# HB-UNI-SenAct-4-4-RC_V2_0.net
KiCad netlist of a schematic drawn in EAGLE
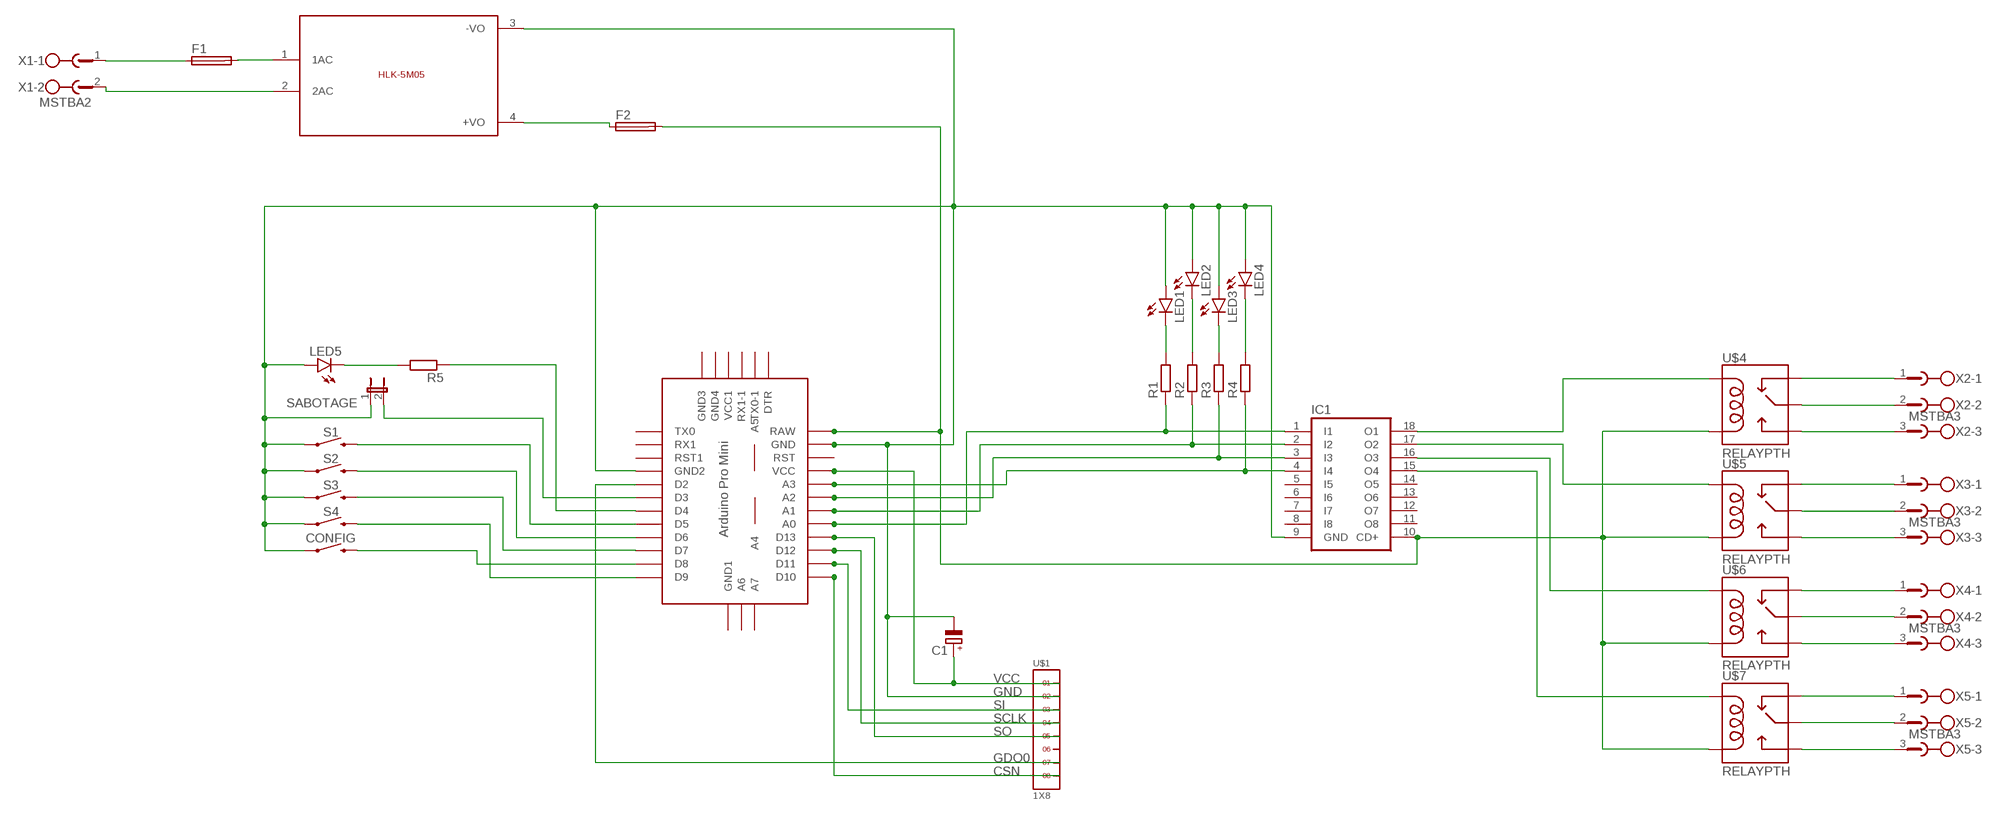
[diagram p0: schematic, sheet 1]

(export (version "E")
  (design (tool "Eeschema 10.0.6"))
  (components
    (comp (ref "C1")
      (value "CPOL-EUE2.5-5")
      (footprint "eagle-import:E2,5-5")
      (libsource (lib "eagle-import") (part "CPOL-EUE2.5-5"))
    )
    (comp (ref "CONFIG")
      (value "MOMENTARY-SWITCH-SPST-PTH-6.0MM-KIT")
      (footprint "eagle-import:TACTILE_SWITCH_PTH_6.0MM_KIT")
      (libsource (lib "eagle-import") (part "MOMENTARY-SWITCH-SPST-PTH-6.0MM-KIT"))
    )
    (comp (ref "F1")
      (value "SH22,5A")
      (footprint "eagle-import:SH22,5A")
      (fields (field (name "MPN") "0031.7701.11"))
      (libsource (lib "eagle-import") (part "SH22,5A"))
    )
    (comp (ref "F2")
      (value "SH22,5A")
      (footprint "eagle-import:SH22,5A")
      (fields (field (name "MPN") "0031.7701.11"))
      (libsource (lib "eagle-import") (part "SH22,5A"))
    )
    (comp (ref "IC1")
      (value "ULN2803A")
      (footprint "eagle-import:DIL18")
      (libsource (lib "eagle-import") (part "ULN2803A"))
    )
    (comp (ref "LED1")
      (value "LED3MM")
      (footprint "eagle-import:LED3MM")
      (libsource (lib "eagle-import") (part "LED3MM"))
    )
    (comp (ref "LED2")
      (value "LED3MM")
      (footprint "eagle-import:LED3MM")
      (libsource (lib "eagle-import") (part "LED3MM"))
    )
    (comp (ref "LED3")
      (value "LED3MM")
      (footprint "eagle-import:LED3MM")
      (libsource (lib "eagle-import") (part "LED3MM"))
    )
    (comp (ref "LED4")
      (value "LED3MM")
      (footprint "eagle-import:LED3MM")
      (libsource (lib "eagle-import") (part "LED3MM"))
    )
    (comp (ref "LED5")
      (value "LED3MM")
      (footprint "eagle-import:LED3MM")
      (libsource (lib "eagle-import") (part "LED3MM"))
    )
    (comp (ref "R1")
      (value "R-EU_0309/10")
      (footprint "eagle-import:0309_10")
      (libsource (lib "eagle-import") (part "R-EU_0309/10"))
    )
    (comp (ref "R2")
      (value "R-EU_0309/10")
      (footprint "eagle-import:0309_10")
      (libsource (lib "eagle-import") (part "R-EU_0309/10"))
    )
    (comp (ref "R3")
      (value "R-EU_0309/10")
      (footprint "eagle-import:0309_10")
      (libsource (lib "eagle-import") (part "R-EU_0309/10"))
    )
    (comp (ref "R4")
      (value "R-EU_0309/10")
      (footprint "eagle-import:0309_10")
      (libsource (lib "eagle-import") (part "R-EU_0309/10"))
    )
    (comp (ref "R5")
      (value "R-EU_0309/10")
      (footprint "eagle-import:0309_10")
      (libsource (lib "eagle-import") (part "R-EU_0309/10"))
    )
    (comp (ref "S1")
      (value "MOMENTARY-SWITCH-SPST-PTH-6.0MM-KIT")
      (footprint "eagle-import:TACTILE_SWITCH_PTH_6.0MM_KIT")
      (libsource (lib "eagle-import") (part "MOMENTARY-SWITCH-SPST-PTH-6.0MM-KIT"))
    )
    (comp (ref "S2")
      (value "MOMENTARY-SWITCH-SPST-PTH-6.0MM-KIT")
      (footprint "eagle-import:TACTILE_SWITCH_PTH_6.0MM_KIT")
      (libsource (lib "eagle-import") (part "MOMENTARY-SWITCH-SPST-PTH-6.0MM-KIT"))
    )
    (comp (ref "S3")
      (value "MOMENTARY-SWITCH-SPST-PTH-6.0MM-KIT")
      (footprint "eagle-import:TACTILE_SWITCH_PTH_6.0MM_KIT")
      (libsource (lib "eagle-import") (part "MOMENTARY-SWITCH-SPST-PTH-6.0MM-KIT"))
    )
    (comp (ref "S4")
      (value "MOMENTARY-SWITCH-SPST-PTH-6.0MM-KIT")
      (footprint "eagle-import:TACTILE_SWITCH_PTH_6.0MM_KIT")
      (libsource (lib "eagle-import") (part "MOMENTARY-SWITCH-SPST-PTH-6.0MM-KIT"))
    )
    (comp (ref "SABOTAGE")
      (value "JP1E")
      (footprint "eagle-import:JP1")
      (libsource (lib "eagle-import") (part "JP1E"))
    )
    (comp (ref "U$1")
      (value "1X8")
      (footprint "eagle-import:1X8")
      (libsource (lib "eagle-import") (part "1X8"))
    )
    (comp (ref "U$2")
      (value "ABK-PRO-MINI")
      (footprint "eagle-import:ABK-PRO-MINI")
      (libsource (lib "eagle-import") (part "ABK-PRO-MINI"))
    )
    (comp (ref "U$3")
      (value "5VDC/5W")
      (footprint "eagle-import:HLK-5M05")
      (libsource (lib "eagle-import") (part "HLK-5M05"))
    )
    (comp (ref "U$4")
      (value "RELAYPTH")
      (footprint "eagle-import:SRD-05VDC-SL-C")
      (libsource (lib "eagle-import") (part "RELAYPTH"))
    )
    (comp (ref "U$5")
      (value "RELAYPTH")
      (footprint "eagle-import:SRD-05VDC-SL-C")
      (libsource (lib "eagle-import") (part "RELAYPTH"))
    )
    (comp (ref "U$6")
      (value "RELAYPTH")
      (footprint "eagle-import:SRD-05VDC-SL-C")
      (libsource (lib "eagle-import") (part "RELAYPTH"))
    )
    (comp (ref "U$7")
      (value "RELAYPTH")
      (footprint "eagle-import:SRD-05VDC-SL-C")
      (libsource (lib "eagle-import") (part "RELAYPTH"))
    )
    (comp (ref "X1")
      (value "MSTBA2")
      (footprint "eagle-import:MSTBA2")
      (fields (field (name "MF") "FARNELL") (field (name "MPN") "1757242"))
      (libsource (lib "eagle-import") (part "MSTBA2"))
    )
    (comp (ref "X2")
      (value "MSTBA3")
      (footprint "eagle-import:MSTBA3")
      (fields (field (name "MF") "FARNELL") (field (name "MPN") "1757255"))
      (libsource (lib "eagle-import") (part "MSTBA3"))
    )
    (comp (ref "X3")
      (value "MSTBA3")
      (footprint "eagle-import:MSTBA3")
      (fields (field (name "MF") "FARNELL") (field (name "MPN") "1757255"))
      (libsource (lib "eagle-import") (part "MSTBA3"))
    )
    (comp (ref "X4")
      (value "MSTBA3")
      (footprint "eagle-import:MSTBA3")
      (fields (field (name "MF") "FARNELL") (field (name "MPN") "1757255"))
      (libsource (lib "eagle-import") (part "MSTBA3"))
    )
    (comp (ref "X5")
      (value "MSTBA3")
      (footprint "eagle-import:MSTBA3")
      (fields (field (name "MF") "FARNELL") (field (name "MPN") "1757255"))
      (libsource (lib "eagle-import") (part "MSTBA3"))
    )
  )
  (nets
    (net (code "1") (name "/CSN") (class "Default")
      (node (ref "U$1") (pin "8") (pinfunction "8_8") (pintype "bidirectional"))
      (node (ref "U$2") (pin "D10") (pinfunction "D10_D10") (pintype "bidirectional"))
    )
    (net (code "2") (name "/GDO0") (class "Default")
      (node (ref "U$1") (pin "7") (pinfunction "7_7") (pintype "bidirectional"))
      (node (ref "U$2") (pin "D2") (pinfunction "D2_D2") (pintype "bidirectional"))
    )
    (net (code "3") (name "/GND") (class "Default")
      (node (ref "C1") (pin "-") (pinfunction "-_-") (pintype "passive"))
      (node (ref "CONFIG") (pin "1") (pinfunction "1_1") (pintype "passive"))
      (node (ref "IC1") (pin "9") (pinfunction "GND_9") (pintype "power_in"))
      (node (ref "LED1") (pin "A") (pinfunction "A_A") (pintype "passive"))
      (node (ref "LED2") (pin "A") (pinfunction "A_A") (pintype "passive"))
      (node (ref "LED3") (pin "A") (pinfunction "A_A") (pintype "passive"))
      (node (ref "LED4") (pin "A") (pinfunction "A_A") (pintype "passive"))
      (node (ref "LED5") (pin "A") (pinfunction "A_A") (pintype "passive"))
      (node (ref "S1") (pin "1") (pinfunction "1_1") (pintype "passive"))
      (node (ref "S2") (pin "1") (pinfunction "1_1") (pintype "passive"))
      (node (ref "S3") (pin "1") (pinfunction "1_1") (pintype "passive"))
      (node (ref "S4") (pin "1") (pinfunction "1_1") (pintype "passive"))
      (node (ref "SABOTAGE") (pin "1") (pinfunction "1_1") (pintype "passive"))
      (node (ref "U$1") (pin "2") (pinfunction "2_2") (pintype "bidirectional"))
      (node (ref "U$2") (pin "GND") (pinfunction "GND_GND") (pintype "bidirectional"))
      (node (ref "U$2") (pin "GND1") (pinfunction "GND2_GND1") (pintype "bidirectional"))
      (node (ref "U$3") (pin "3") (pinfunction "-VO_3") (pintype "bidirectional"))
    )
    (net (code "4") (name "/SCLK") (class "Default")
      (node (ref "U$1") (pin "4") (pinfunction "4_4") (pintype "bidirectional"))
      (node (ref "U$2") (pin "D12") (pinfunction "D12_D12") (pintype "bidirectional"))
    )
    (net (code "5") (name "/SI") (class "Default")
      (node (ref "U$1") (pin "3") (pinfunction "3_3") (pintype "bidirectional"))
      (node (ref "U$2") (pin "D11") (pinfunction "D11_D11") (pintype "bidirectional"))
    )
    (net (code "6") (name "/SO") (class "Default")
      (node (ref "U$1") (pin "5") (pinfunction "5_5") (pintype "bidirectional"))
      (node (ref "U$2") (pin "D13") (pinfunction "D13_D13") (pintype "bidirectional"))
    )
    (net (code "7") (name "/VCC") (class "Default")
      (node (ref "C1") (pin "+") (pinfunction "+_+") (pintype "passive"))
      (node (ref "U$1") (pin "1") (pinfunction "1_1") (pintype "bidirectional"))
      (node (ref "U$2") (pin "VCC") (pinfunction "VCC_VCC") (pintype "bidirectional"))
    )
    (net (code "8") (name "Net-(CONFIG-2)") (class "Default")
      (node (ref "CONFIG") (pin "3") (pinfunction "2_3") (pintype "passive"))
      (node (ref "U$2") (pin "D8") (pinfunction "D8_D8") (pintype "bidirectional"))
    )
    (net (code "9") (name "Net-(F1-Pad1)") (class "Default")
      (node (ref "F1") (pin "1") (pinfunction "1_1") (pintype "passive"))
      (node (ref "X1") (pin "1") (pinfunction "1_1") (pintype "passive"))
    )
    (net (code "10") (name "Net-(IC1-CD+)") (class "Default")
      (node (ref "F2") (pin "2") (pinfunction "2_2") (pintype "passive"))
      (node (ref "IC1") (pin "10") (pinfunction "CD+_10") (pintype "passive"))
      (node (ref "U$2") (pin "RAW") (pinfunction "RAW_RAW") (pintype "bidirectional"))
      (node (ref "U$4") (pin "COIL0") (pinfunction "COIL0_COIL0") (pintype "bidirectional"))
      (node (ref "U$5") (pin "COIL0") (pinfunction "COIL0_COIL0") (pintype "bidirectional"))
      (node (ref "U$6") (pin "COIL0") (pinfunction "COIL0_COIL0") (pintype "bidirectional"))
      (node (ref "U$7") (pin "COIL0") (pinfunction "COIL0_COIL0") (pintype "bidirectional"))
    )
    (net (code "11") (name "Net-(IC1-I1)") (class "Default")
      (node (ref "IC1") (pin "1") (pinfunction "I1_1") (pintype "input"))
      (node (ref "R1") (pin "1") (pinfunction "1_1") (pintype "passive"))
      (node (ref "U$2") (pin "A0") (pinfunction "A0_A0") (pintype "bidirectional"))
    )
    (net (code "12") (name "Net-(IC1-I2)") (class "Default")
      (node (ref "IC1") (pin "2") (pinfunction "I2_2") (pintype "input"))
      (node (ref "R2") (pin "1") (pinfunction "1_1") (pintype "passive"))
      (node (ref "U$2") (pin "A1") (pinfunction "A1_A1") (pintype "bidirectional"))
    )
    (net (code "13") (name "Net-(IC1-I3)") (class "Default")
      (node (ref "IC1") (pin "3") (pinfunction "I3_3") (pintype "input"))
      (node (ref "R3") (pin "1") (pinfunction "1_1") (pintype "passive"))
      (node (ref "U$2") (pin "A2") (pinfunction "A2_A2") (pintype "bidirectional"))
    )
    (net (code "14") (name "Net-(IC1-I4)") (class "Default")
      (node (ref "IC1") (pin "4") (pinfunction "I4_4") (pintype "input"))
      (node (ref "R4") (pin "1") (pinfunction "1_1") (pintype "passive"))
      (node (ref "U$2") (pin "A3") (pinfunction "A3_A3") (pintype "bidirectional"))
    )
    (net (code "15") (name "Net-(IC1-O1)") (class "Default")
      (node (ref "IC1") (pin "18") (pinfunction "O1_18") (pintype "open_collector"))
      (node (ref "U$4") (pin "COIL1") (pinfunction "COIL1_COIL1") (pintype "bidirectional"))
    )
    (net (code "16") (name "Net-(IC1-O2)") (class "Default")
      (node (ref "IC1") (pin "17") (pinfunction "O2_17") (pintype "open_collector"))
      (node (ref "U$5") (pin "COIL1") (pinfunction "COIL1_COIL1") (pintype "bidirectional"))
    )
    (net (code "17") (name "Net-(IC1-O3)") (class "Default")
      (node (ref "IC1") (pin "16") (pinfunction "O3_16") (pintype "open_collector"))
      (node (ref "U$6") (pin "COIL1") (pinfunction "COIL1_COIL1") (pintype "bidirectional"))
    )
    (net (code "18") (name "Net-(IC1-O4)") (class "Default")
      (node (ref "IC1") (pin "15") (pinfunction "O4_15") (pintype "open_collector"))
      (node (ref "U$7") (pin "COIL1") (pinfunction "COIL1_COIL1") (pintype "bidirectional"))
    )
    (net (code "19") (name "Net-(LED1-C)") (class "Default")
      (node (ref "LED1") (pin "K") (pinfunction "C_K") (pintype "passive"))
      (node (ref "R1") (pin "2") (pinfunction "2_2") (pintype "passive"))
    )
    (net (code "20") (name "Net-(LED2-C)") (class "Default")
      (node (ref "LED2") (pin "K") (pinfunction "C_K") (pintype "passive"))
      (node (ref "R2") (pin "2") (pinfunction "2_2") (pintype "passive"))
    )
    (net (code "21") (name "Net-(LED3-C)") (class "Default")
      (node (ref "LED3") (pin "K") (pinfunction "C_K") (pintype "passive"))
      (node (ref "R3") (pin "2") (pinfunction "2_2") (pintype "passive"))
    )
    (net (code "22") (name "Net-(LED4-C)") (class "Default")
      (node (ref "LED4") (pin "K") (pinfunction "C_K") (pintype "passive"))
      (node (ref "R4") (pin "2") (pinfunction "2_2") (pintype "passive"))
    )
    (net (code "23") (name "Net-(LED5-C)") (class "Default")
      (node (ref "LED5") (pin "K") (pinfunction "C_K") (pintype "passive"))
      (node (ref "R5") (pin "2") (pinfunction "2_2") (pintype "passive"))
    )
    (net (code "24") (name "Net-(R5-Pad1)") (class "Default")
      (node (ref "R5") (pin "1") (pinfunction "1_1") (pintype "passive"))
      (node (ref "U$2") (pin "D4") (pinfunction "D4_D4") (pintype "bidirectional"))
    )
    (net (code "25") (name "Net-(S1-2)") (class "Default")
      (node (ref "S1") (pin "3") (pinfunction "2_3") (pintype "passive"))
      (node (ref "U$2") (pin "D5") (pinfunction "D5_D5") (pintype "bidirectional"))
    )
    (net (code "26") (name "Net-(S2-2)") (class "Default")
      (node (ref "S2") (pin "3") (pinfunction "2_3") (pintype "passive"))
      (node (ref "U$2") (pin "D6") (pinfunction "D6_D6") (pintype "bidirectional"))
    )
    (net (code "27") (name "Net-(S3-2)") (class "Default")
      (node (ref "S3") (pin "3") (pinfunction "2_3") (pintype "passive"))
      (node (ref "U$2") (pin "D7") (pinfunction "D7_D7") (pintype "bidirectional"))
    )
    (net (code "28") (name "Net-(S4-2)") (class "Default")
      (node (ref "S4") (pin "3") (pinfunction "2_3") (pintype "passive"))
      (node (ref "U$2") (pin "D9") (pinfunction "D9_D9") (pintype "bidirectional"))
    )
    (net (code "29") (name "Net-(SABOTAGE-Pad2)") (class "Default")
      (node (ref "SABOTAGE") (pin "2") (pinfunction "2_2") (pintype "passive"))
      (node (ref "U$2") (pin "D3") (pinfunction "D3_D3") (pintype "bidirectional"))
    )
    (net (code "30") (name "Net-(U$3-+VO)") (class "Default")
      (node (ref "F2") (pin "1") (pinfunction "1_1") (pintype "passive"))
      (node (ref "U$3") (pin "4") (pinfunction "+VO_4") (pintype "bidirectional"))
    )
    (net (code "31") (name "Net-(U$3-1AC)") (class "Default")
      (node (ref "F1") (pin "2") (pinfunction "2_2") (pintype "passive"))
      (node (ref "U$3") (pin "1") (pinfunction "1AC_1") (pintype "bidirectional"))
    )
    (net (code "32") (name "Net-(U$3-2AC)") (class "Default")
      (node (ref "U$3") (pin "2") (pinfunction "2AC_2") (pintype "bidirectional"))
      (node (ref "X1") (pin "2") (pinfunction "1_2") (pintype "passive"))
    )
    (net (code "33") (name "Net-(U$4-SWCLOSE)") (class "Default")
      (node (ref "U$4") (pin "SWCLOSED") (pinfunction "SWCLOSE_SWCLOSED") (pintype "bidirectional"))
      (node (ref "X2") (pin "1") (pinfunction "1_1") (pintype "passive"))
    )
    (net (code "34") (name "Net-(U$5-SWCLOSE)") (class "Default")
      (node (ref "U$5") (pin "SWCLOSED") (pinfunction "SWCLOSE_SWCLOSED") (pintype "bidirectional"))
      (node (ref "X3") (pin "1") (pinfunction "1_1") (pintype "passive"))
    )
    (net (code "35") (name "Net-(U$6-SWCLOSE)") (class "Default")
      (node (ref "U$6") (pin "SWCLOSED") (pinfunction "SWCLOSE_SWCLOSED") (pintype "bidirectional"))
      (node (ref "X4") (pin "1") (pinfunction "1_1") (pintype "passive"))
    )
    (net (code "36") (name "Net-(U$7-SWCLOSE)") (class "Default")
      (node (ref "U$7") (pin "SWCLOSED") (pinfunction "SWCLOSE_SWCLOSED") (pintype "bidirectional"))
      (node (ref "X5") (pin "1") (pinfunction "1_1") (pintype "passive"))
    )
    (net (code "37") (name "Net-(X2B-1)") (class "Default")
      (node (ref "U$4") (pin "SWCOMMON") (pinfunction "SWCOMMON_SWCOMMON") (pintype "bidirectional"))
      (node (ref "X2") (pin "2") (pinfunction "1_2") (pintype "passive"))
    )
    (net (code "38") (name "Net-(X2C-1)") (class "Default")
      (node (ref "U$4") (pin "SWOPEN") (pinfunction "SWOPEN_SWOPEN") (pintype "bidirectional"))
      (node (ref "X2") (pin "3") (pinfunction "1_3") (pintype "passive"))
    )
    (net (code "39") (name "Net-(X3B-1)") (class "Default")
      (node (ref "U$5") (pin "SWCOMMON") (pinfunction "SWCOMMON_SWCOMMON") (pintype "bidirectional"))
      (node (ref "X3") (pin "2") (pinfunction "1_2") (pintype "passive"))
    )
    (net (code "40") (name "Net-(X3C-1)") (class "Default")
      (node (ref "U$5") (pin "SWOPEN") (pinfunction "SWOPEN_SWOPEN") (pintype "bidirectional"))
      (node (ref "X3") (pin "3") (pinfunction "1_3") (pintype "passive"))
    )
    (net (code "41") (name "Net-(X4B-1)") (class "Default")
      (node (ref "U$6") (pin "SWCOMMON") (pinfunction "SWCOMMON_SWCOMMON") (pintype "bidirectional"))
      (node (ref "X4") (pin "2") (pinfunction "1_2") (pintype "passive"))
    )
    (net (code "42") (name "Net-(X4C-1)") (class "Default")
      (node (ref "U$6") (pin "SWOPEN") (pinfunction "SWOPEN_SWOPEN") (pintype "bidirectional"))
      (node (ref "X4") (pin "3") (pinfunction "1_3") (pintype "passive"))
    )
    (net (code "43") (name "Net-(X5B-1)") (class "Default")
      (node (ref "U$7") (pin "SWCOMMON") (pinfunction "SWCOMMON_SWCOMMON") (pintype "bidirectional"))
      (node (ref "X5") (pin "2") (pinfunction "1_2") (pintype "passive"))
    )
    (net (code "44") (name "Net-(X5C-1)") (class "Default")
      (node (ref "U$7") (pin "SWOPEN") (pinfunction "SWOPEN_SWOPEN") (pintype "bidirectional"))
      (node (ref "X5") (pin "3") (pinfunction "1_3") (pintype "passive"))
    )
    (net (code "45") (name "unconnected-(IC1-I5-Pad5)") (class "Default")
      (node (ref "IC1") (pin "5") (pinfunction "I5_5") (pintype "input"))
    )
    (net (code "46") (name "unconnected-(IC1-I6-Pad6)") (class "Default")
      (node (ref "IC1") (pin "6") (pinfunction "I6_6") (pintype "input"))
    )
    (net (code "47") (name "unconnected-(IC1-I7-Pad7)") (class "Default")
      (node (ref "IC1") (pin "7") (pinfunction "I7_7") (pintype "input"))
    )
    (net (code "48") (name "unconnected-(IC1-I8-Pad8)") (class "Default")
      (node (ref "IC1") (pin "8") (pinfunction "I8_8") (pintype "input"))
    )
    (net (code "49") (name "unconnected-(IC1-O5-Pad14)") (class "Default")
      (node (ref "IC1") (pin "14") (pinfunction "O5_14") (pintype "open_collector"))
    )
    (net (code "50") (name "unconnected-(IC1-O6-Pad13)") (class "Default")
      (node (ref "IC1") (pin "13") (pinfunction "O6_13") (pintype "open_collector"))
    )
    (net (code "51") (name "unconnected-(IC1-O7-Pad12)") (class "Default")
      (node (ref "IC1") (pin "12") (pinfunction "O7_12") (pintype "open_collector"))
    )
    (net (code "52") (name "unconnected-(IC1-O8-Pad11)") (class "Default")
      (node (ref "IC1") (pin "11") (pinfunction "O8_11") (pintype "open_collector"))
    )
    (net (code "53") (name "unconnected-(U$1-Pad6)") (class "Default")
      (node (ref "U$1") (pin "6") (pinfunction "6_6") (pintype "bidirectional"))
    )
    (net (code "54") (name "unconnected-(U$2-GND1-PadGND4)") (class "Default")
      (node (ref "U$2") (pin "GND4") (pinfunction "GND1_GND4") (pintype "bidirectional"))
    )
    (net (code "55") (name "unconnected-(U$2-GND3-PadGND2)") (class "Default")
      (node (ref "U$2") (pin "GND2") (pinfunction "GND3_GND2") (pintype "bidirectional"))
    )
    (net (code "56") (name "unconnected-(U$2-GND4-PadGND3)") (class "Default")
      (node (ref "U$2") (pin "GND3") (pinfunction "GND4_GND3") (pintype "bidirectional"))
    )
    (net (code "57") (name "unconnected-(U$2-PadA4)") (class "Default")
      (node (ref "U$2") (pin "A4") (pinfunction "A4_A4") (pintype "bidirectional"))
    )
    (net (code "58") (name "unconnected-(U$2-PadA5)") (class "Default")
      (node (ref "U$2") (pin "A5") (pinfunction "A5_A5") (pintype "bidirectional"))
    )
    (net (code "59") (name "unconnected-(U$2-PadA6)") (class "Default")
      (node (ref "U$2") (pin "A6") (pinfunction "A6_A6") (pintype "bidirectional"))
    )
    (net (code "60") (name "unconnected-(U$2-PadA7)") (class "Default")
      (node (ref "U$2") (pin "A7") (pinfunction "A7_A7") (pintype "bidirectional"))
    )
    (net (code "61") (name "unconnected-(U$2-PadDTR)") (class "Default")
      (node (ref "U$2") (pin "DTR") (pinfunction "DTR_DTR") (pintype "bidirectional"))
    )
    (net (code "62") (name "unconnected-(U$2-PadRST)") (class "Default")
      (node (ref "U$2") (pin "RST") (pinfunction "RST_RST") (pintype "bidirectional"))
    )
    (net (code "63") (name "unconnected-(U$2-PadRST1)") (class "Default")
      (node (ref "U$2") (pin "RST1") (pinfunction "RST1_RST1") (pintype "bidirectional"))
    )
    (net (code "64") (name "unconnected-(U$2-PadRX1)") (class "Default")
      (node (ref "U$2") (pin "RX1") (pinfunction "RX1_RX1") (pintype "bidirectional"))
    )
    (net (code "65") (name "unconnected-(U$2-PadRX1-1)") (class "Default")
      (node (ref "U$2") (pin "RX1-1") (pinfunction "RX1-1_RX1-1") (pintype "bidirectional"))
    )
    (net (code "66") (name "unconnected-(U$2-PadTX0)") (class "Default")
      (node (ref "U$2") (pin "TX0") (pinfunction "TX0_TX0") (pintype "bidirectional"))
    )
    (net (code "67") (name "unconnected-(U$2-PadTX0-1)") (class "Default")
      (node (ref "U$2") (pin "TX0-1") (pinfunction "TX0-1_TX0-1") (pintype "bidirectional"))
    )
    (net (code "68") (name "unconnected-(U$2-PadVCC1)") (class "Default")
      (node (ref "U$2") (pin "VCC1") (pinfunction "VCC1_VCC1") (pintype "bidirectional"))
    )
  )
)
